# Analog_Testvoltage_Output.net
KiCad netlist of a schematic drawn in Altium Designer
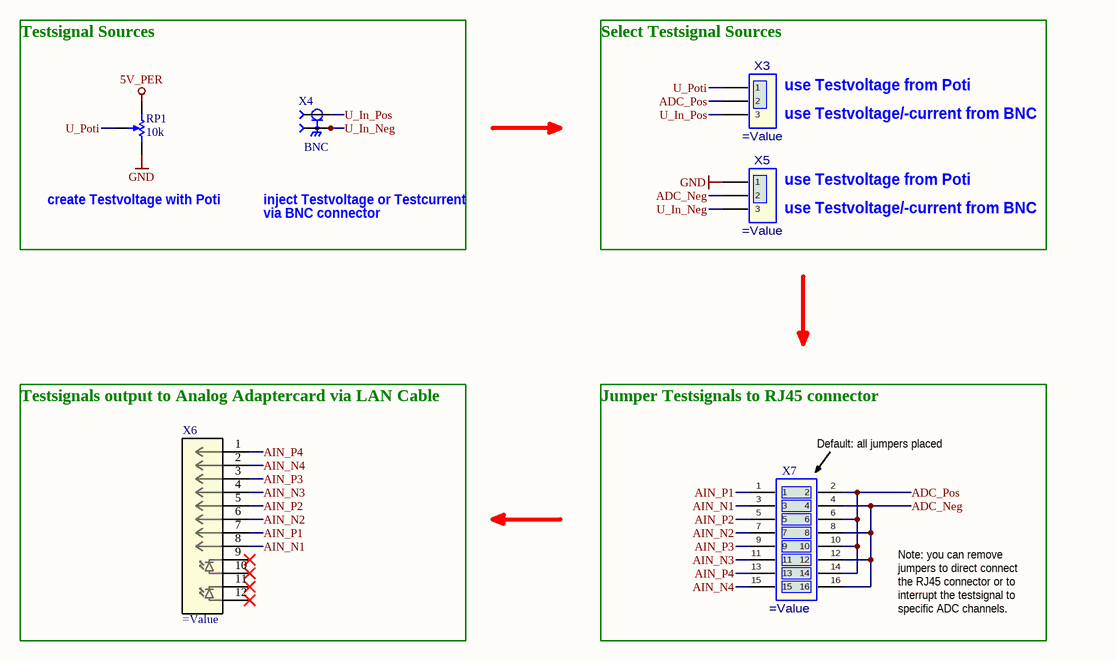
[diagram p0: Analog_Testvoltage_Output.SchDoc]

(export (version "E")
  (design (tool "Eeschema 10.0.6"))
  (components
    (comp (ref "RP1")
      (value "10k")
      (footprint "BOURNS_3299W-3_V")
      (fields
        (field (name "MF") "Bourns")
        (field (name "MPN") "3299W-1-103LF")
        (field (name "CREATED") "2020_12_15_AGeiger")
      )
      (libsource (lib "UZ_A_Testboard") (part "Trimmer_3299W"))
    )
    (comp (ref "X3")
      (value "~")
      (footprint "TSW-103-XX-XXX-S")
      (description ".025[0.64] SQ. POST TERMINAL STRIP ASSEMBLY.")
      (fields
        (field (name "MANUFACTURER") "SAMTEC")
        (field (name "MPN") "TSW-103-07-F-S")
        (field (name "CREATED") "2020_11_26_AGeiger")
      )
      (libsource (lib "UZ_A_Testboard") (part "TSW-103-XX-XXX-S"))
    )
    (comp (ref "X4")
      (value "BNC")
      (footprint "SAMTEC_BNC7T-J-P-XX-RA-BH1")
      (description "BNC Connector Jack, Female Socket 75Ohm Panel Mount, Through Hole, Right Angle Solder")
      (fields
        (field (name "MPN") "BNC7T-J-P-HN-RA-BH1")
        (field (name "MF") "Samtec")
        (field (name "CREATED") "2021_04_06_AGeiger")
      )
      (libsource (lib "UZ_A_Testboard") (part "BNC7T-J-P-XX-RA-BH1"))
    )
    (comp (ref "X5")
      (value "~")
      (footprint "TSW-103-XX-XXX-S")
      (description ".025[0.64] SQ. POST TERMINAL STRIP ASSEMBLY.")
      (fields
        (field (name "MANUFACTURER") "SAMTEC")
        (field (name "MPN") "TSW-103-07-F-S")
        (field (name "CREATED") "2020_11_26_AGeiger")
      )
      (libsource (lib "UZ_A_Testboard") (part "TSW-103-XX-XXX-S"))
    )
    (comp (ref "X6")
      (value "~")
      (footprint "RJ45_RJHSE-5384_AMP")
      (description "RJ45 without integrated trafos")
      (fields
        (field (name "MF") "Amphenol")
        (field (name "MPN") "RJHSE-5381")
        (field (name "CREATED") "2021_03_11_AGeiger")
      )
      (libsource (lib "UZ_A_Testboard") (part "RJHSE-5381"))
    )
    (comp (ref "X7")
      (value "~")
      (footprint "TSW-108-XX-XXX-D")
      (description "Pin Header, 2.54mm")
      (fields
        (field (name "MF") "SAMTEC")
        (field (name "MPN") "TSW-108-07-F-D")
        (field (name "CREATED") "2019_02_10_AGeiger")
      )
      (libsource (lib "UZ_A_Testboard") (part "TSW-108-XX-XXX-D"))
    )
  )
  (nets
    (net (code "1") (name "/ADC_Neg") (class "Default")
      (node (ref "X5") (pin "2") (pinfunction "2_2") (pintype "passive"))
      (node (ref "X7") (pin "12") (pinfunction "12_12") (pintype "passive"))
      (node (ref "X7") (pin "16") (pinfunction "16_16") (pintype "passive"))
      (node (ref "X7") (pin "4") (pinfunction "4_4") (pintype "passive"))
      (node (ref "X7") (pin "8") (pinfunction "8_8") (pintype "passive"))
    )
    (net (code "2") (name "/ADC_Pos") (class "Default")
      (node (ref "X3") (pin "2") (pinfunction "2_2") (pintype "passive"))
      (node (ref "X7") (pin "10") (pinfunction "10_10") (pintype "passive"))
      (node (ref "X7") (pin "14") (pinfunction "14_14") (pintype "passive"))
      (node (ref "X7") (pin "2") (pinfunction "2_2") (pintype "passive"))
      (node (ref "X7") (pin "6") (pinfunction "6_6") (pintype "passive"))
    )
    (net (code "3") (name "/AIN_N1") (class "Default")
      (node (ref "X6") (pin "8") (pinfunction "8_8") (pintype "passive"))
      (node (ref "X7") (pin "3") (pinfunction "3_3") (pintype "passive"))
    )
    (net (code "4") (name "/AIN_N2") (class "Default")
      (node (ref "X6") (pin "6") (pinfunction "6_6") (pintype "passive"))
      (node (ref "X7") (pin "7") (pinfunction "7_7") (pintype "passive"))
    )
    (net (code "5") (name "/AIN_N3") (class "Default")
      (node (ref "X6") (pin "4") (pinfunction "4_4") (pintype "passive"))
      (node (ref "X7") (pin "11") (pinfunction "11_11") (pintype "passive"))
    )
    (net (code "6") (name "/AIN_N4") (class "Default")
      (node (ref "X6") (pin "2") (pinfunction "2_2") (pintype "passive"))
      (node (ref "X7") (pin "15") (pinfunction "15_15") (pintype "passive"))
    )
    (net (code "7") (name "/AIN_P1") (class "Default")
      (node (ref "X6") (pin "7") (pinfunction "7_7") (pintype "passive"))
      (node (ref "X7") (pin "1") (pinfunction "1_1") (pintype "passive"))
    )
    (net (code "8") (name "/AIN_P2") (class "Default")
      (node (ref "X6") (pin "5") (pinfunction "5_5") (pintype "passive"))
      (node (ref "X7") (pin "5") (pinfunction "5_5") (pintype "passive"))
    )
    (net (code "9") (name "/AIN_P3") (class "Default")
      (node (ref "X6") (pin "3") (pinfunction "3_3") (pintype "passive"))
      (node (ref "X7") (pin "9") (pinfunction "9_9") (pintype "passive"))
    )
    (net (code "10") (name "/AIN_P4") (class "Default")
      (node (ref "X6") (pin "1") (pinfunction "1_1") (pintype "passive"))
      (node (ref "X7") (pin "13") (pinfunction "13_13") (pintype "passive"))
    )
    (net (code "11") (name "/U_In_Neg") (class "Default")
      (node (ref "X4") (pin "S1") (pinfunction "2_S1") (pintype "passive"))
      (node (ref "X4") (pin "S2") (pinfunction "2_S2") (pintype "passive"))
      (node (ref "X4") (pin "S3") (pinfunction "2_S3") (pintype "passive"))
      (node (ref "X4") (pin "S4") (pinfunction "2_S4") (pintype "passive"))
      (node (ref "X5") (pin "3") (pinfunction "3_3") (pintype "passive"))
    )
    (net (code "12") (name "/U_In_Pos") (class "Default")
      (node (ref "X3") (pin "3") (pinfunction "3_3") (pintype "passive"))
      (node (ref "X4") (pin "1") (pinfunction "1_1") (pintype "passive"))
    )
    (net (code "13") (name "/U_Poti") (class "Default")
      (node (ref "RP1") (pin "2") (pinfunction "2_2") (pintype "passive"))
      (node (ref "X3") (pin "1") (pinfunction "1_1") (pintype "passive"))
    )
    (net (code "14") (name "5V_PER") (class "Default")
      (node (ref "RP1") (pin "1") (pinfunction "1_1") (pintype "passive"))
    )
    (net (code "15") (name "GND") (class "Default")
      (node (ref "RP1") (pin "3") (pinfunction "3_3") (pintype "passive"))
      (node (ref "X5") (pin "1") (pinfunction "1_1") (pintype "passive"))
    )
    (net (code "16") (name "unconnected-(X6-Pad9)") (class "Default")
      (node (ref "X6") (pin "9") (pinfunction "9_9") (pintype "passive+no_connect"))
    )
    (net (code "17") (name "unconnected-(X6-Pad10)") (class "Default")
      (node (ref "X6") (pin "10") (pinfunction "10_10") (pintype "passive+no_connect"))
    )
    (net (code "18") (name "unconnected-(X6-Pad11)") (class "Default")
      (node (ref "X6") (pin "11") (pinfunction "11_11") (pintype "passive+no_connect"))
    )
    (net (code "19") (name "unconnected-(X6-Pad12)") (class "Default")
      (node (ref "X6") (pin "12") (pinfunction "12_12") (pintype "passive+no_connect"))
    )
  )
)
